# DIGITAL_OUTPUT1.net
KiCad netlist of a schematic drawn in Altium Designer
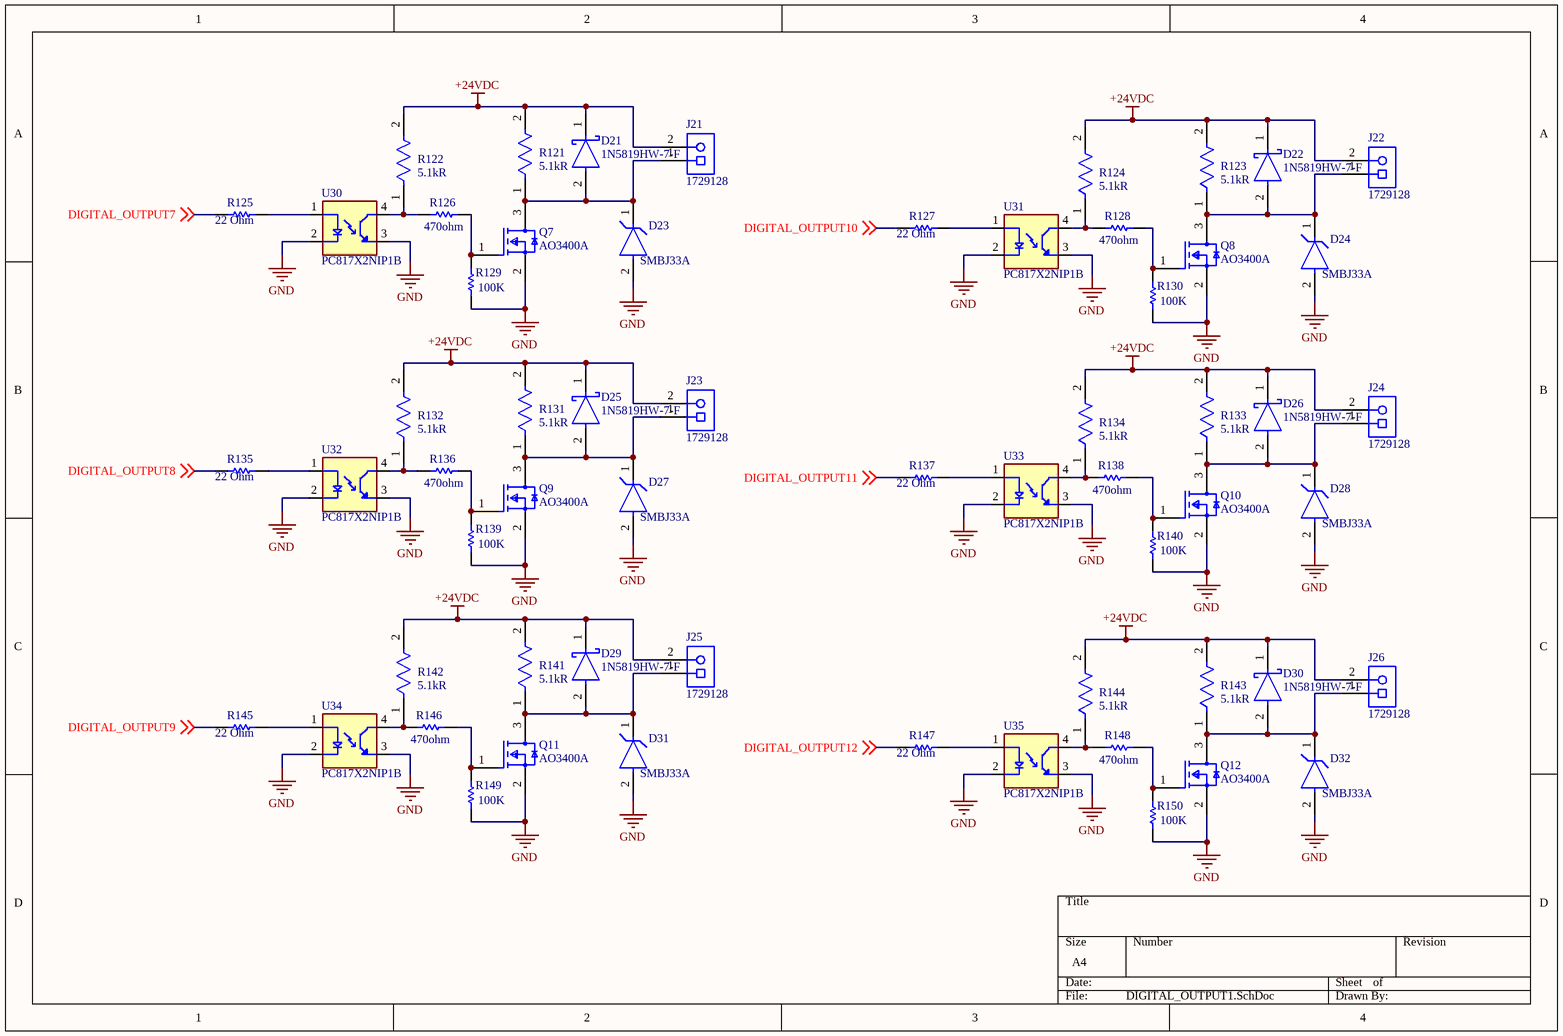
[diagram p0: DIGITAL_OUTPUT1.SchDoc]

(export (version "E")
  (design (tool "Eeschema 10.0.6"))
  (components
    (comp (ref "D21")
      (value "1N5819HW-7-F")
      (footprint "FP-SOD123-IPC_A")
      (description "DIODE SCHOTTKY 40V 1A SOD123")
      (libsource (lib "Altium Content Vault") (part "1d6ec82d83fb6aee721767c19dac4b9"))
    )
    (comp (ref "D22")
      (value "1N5819HW-7-F")
      (footprint "FP-SOD123-IPC_A")
      (description "DIODE SCHOTTKY 40V 1A SOD123")
      (libsource (lib "Altium Content Vault") (part "1d6ec82d83fb6aee721767c19dac4b9"))
    )
    (comp (ref "D23")
      (value "SMBJ33A")
      (footprint "FP-SMBJ-MFG")
      (description "TVS DIODE 33V 53.3V DO214AA")
      (fields
        (field (name "MANUFACTURER") "Littelfuse Inc")
        (field (name "OCTOPART") "https://octopart.com/smbj33a-littelfuse-350829")
      )
      (libsource (lib "Altium Content Vault") (part "f813f71cba58e380607f5dd3caf9714"))
    )
    (comp (ref "D24")
      (value "SMBJ33A")
      (footprint "FP-SMBJ-MFG")
      (description "TVS DIODE 33V 53.3V DO214AA")
      (fields
        (field (name "MANUFACTURER") "Littelfuse Inc")
        (field (name "OCTOPART") "https://octopart.com/smbj33a-littelfuse-350829")
      )
      (libsource (lib "Altium Content Vault") (part "f813f71cba58e380607f5dd3caf9714"))
    )
    (comp (ref "D25")
      (value "1N5819HW-7-F")
      (footprint "FP-SOD123-IPC_A")
      (description "DIODE SCHOTTKY 40V 1A SOD123")
      (libsource (lib "Altium Content Vault") (part "1d6ec82d83fb6aee721767c19dac4b9"))
    )
    (comp (ref "D26")
      (value "1N5819HW-7-F")
      (footprint "FP-SOD123-IPC_A")
      (description "DIODE SCHOTTKY 40V 1A SOD123")
      (libsource (lib "Altium Content Vault") (part "1d6ec82d83fb6aee721767c19dac4b9"))
    )
    (comp (ref "D27")
      (value "SMBJ33A")
      (footprint "FP-SMBJ-MFG")
      (description "TVS DIODE 33V 53.3V DO214AA")
      (fields
        (field (name "MANUFACTURER") "Littelfuse Inc")
        (field (name "OCTOPART") "https://octopart.com/smbj33a-littelfuse-350829")
      )
      (libsource (lib "Altium Content Vault") (part "f813f71cba58e380607f5dd3caf9714"))
    )
    (comp (ref "D28")
      (value "SMBJ33A")
      (footprint "FP-SMBJ-MFG")
      (description "TVS DIODE 33V 53.3V DO214AA")
      (fields
        (field (name "MANUFACTURER") "Littelfuse Inc")
        (field (name "OCTOPART") "https://octopart.com/smbj33a-littelfuse-350829")
      )
      (libsource (lib "Altium Content Vault") (part "f813f71cba58e380607f5dd3caf9714"))
    )
    (comp (ref "D29")
      (value "1N5819HW-7-F")
      (footprint "FP-SOD123-IPC_A")
      (description "DIODE SCHOTTKY 40V 1A SOD123")
      (libsource (lib "Altium Content Vault") (part "1d6ec82d83fb6aee721767c19dac4b9"))
    )
    (comp (ref "D30")
      (value "1N5819HW-7-F")
      (footprint "FP-SOD123-IPC_A")
      (description "DIODE SCHOTTKY 40V 1A SOD123")
      (libsource (lib "Altium Content Vault") (part "1d6ec82d83fb6aee721767c19dac4b9"))
    )
    (comp (ref "D31")
      (value "SMBJ33A")
      (footprint "FP-SMBJ-MFG")
      (description "TVS DIODE 33V 53.3V DO214AA")
      (fields
        (field (name "MANUFACTURER") "Littelfuse Inc")
        (field (name "OCTOPART") "https://octopart.com/smbj33a-littelfuse-350829")
      )
      (libsource (lib "Altium Content Vault") (part "f813f71cba58e380607f5dd3caf9714"))
    )
    (comp (ref "D32")
      (value "SMBJ33A")
      (footprint "FP-SMBJ-MFG")
      (description "TVS DIODE 33V 53.3V DO214AA")
      (fields
        (field (name "MANUFACTURER") "Littelfuse Inc")
        (field (name "OCTOPART") "https://octopart.com/smbj33a-littelfuse-350829")
      )
      (libsource (lib "Altium Content Vault") (part "f813f71cba58e380607f5dd3caf9714"))
    )
    (comp (ref "J21")
      (value "1729128")
      (footprint "PHOE-1729128-2_V")
      (description "PCB Terminal Block, 13.5 A, 400 V, 2-Pin THD, RoHS, Bulk")
      (fields (field (name "MANUFACTURER") "Phoenix Contact"))
      (libsource (lib "Altium Content Vault") (part "CN-2P-F-R2"))
    )
    (comp (ref "J22")
      (value "1729128")
      (footprint "PHOE-1729128-2_V")
      (description "PCB Terminal Block, 13.5 A, 400 V, 2-Pin THD, RoHS, Bulk")
      (fields (field (name "MANUFACTURER") "Phoenix Contact"))
      (libsource (lib "Altium Content Vault") (part "CN-2P-F-R2"))
    )
    (comp (ref "J23")
      (value "1729128")
      (footprint "PHOE-1729128-2_V")
      (description "PCB Terminal Block, 13.5 A, 400 V, 2-Pin THD, RoHS, Bulk")
      (fields (field (name "MANUFACTURER") "Phoenix Contact"))
      (libsource (lib "Altium Content Vault") (part "CN-2P-F-R2"))
    )
    (comp (ref "J24")
      (value "1729128")
      (footprint "PHOE-1729128-2_V")
      (description "PCB Terminal Block, 13.5 A, 400 V, 2-Pin THD, RoHS, Bulk")
      (fields (field (name "MANUFACTURER") "Phoenix Contact"))
      (libsource (lib "Altium Content Vault") (part "CN-2P-F-R2"))
    )
    (comp (ref "J25")
      (value "1729128")
      (footprint "PHOE-1729128-2_V")
      (description "PCB Terminal Block, 13.5 A, 400 V, 2-Pin THD, RoHS, Bulk")
      (fields (field (name "MANUFACTURER") "Phoenix Contact"))
      (libsource (lib "Altium Content Vault") (part "CN-2P-F-R2"))
    )
    (comp (ref "J26")
      (value "1729128")
      (footprint "PHOE-1729128-2_V")
      (description "PCB Terminal Block, 13.5 A, 400 V, 2-Pin THD, RoHS, Bulk")
      (fields (field (name "MANUFACTURER") "Phoenix Contact"))
      (libsource (lib "Altium Content Vault") (part "CN-2P-F-R2"))
    )
    (comp (ref "Q7")
      (value "AO3400A")
      (footprint "FP-SOT23-MFG")
      (description "MOSFET N-CH 30V 5.7A SOT23")
      (libsource (lib "Altium Content Vault") (part "0a9ea7c96deaaede766a5b531c28de0"))
    )
    (comp (ref "Q8")
      (value "AO3400A")
      (footprint "FP-SOT23-MFG")
      (description "MOSFET N-CH 30V 5.7A SOT23")
      (libsource (lib "Altium Content Vault") (part "0a9ea7c96deaaede766a5b531c28de0"))
    )
    (comp (ref "Q9")
      (value "AO3400A")
      (footprint "FP-SOT23-MFG")
      (description "MOSFET N-CH 30V 5.7A SOT23")
      (libsource (lib "Altium Content Vault") (part "0a9ea7c96deaaede766a5b531c28de0"))
    )
    (comp (ref "Q10")
      (value "AO3400A")
      (footprint "FP-SOT23-MFG")
      (description "MOSFET N-CH 30V 5.7A SOT23")
      (libsource (lib "Altium Content Vault") (part "0a9ea7c96deaaede766a5b531c28de0"))
    )
    (comp (ref "Q11")
      (value "AO3400A")
      (footprint "FP-SOT23-MFG")
      (description "MOSFET N-CH 30V 5.7A SOT23")
      (libsource (lib "Altium Content Vault") (part "0a9ea7c96deaaede766a5b531c28de0"))
    )
    (comp (ref "Q12")
      (value "AO3400A")
      (footprint "FP-SOT23-MFG")
      (description "MOSFET N-CH 30V 5.7A SOT23")
      (libsource (lib "Altium Content Vault") (part "0a9ea7c96deaaede766a5b531c28de0"))
    )
    (comp (ref "R121")
      (value "CRCW06035K10FKEA")
      (footprint "FP-CRCW0603-e3-IPC_C")
      (description "RES Thick Film, 5.1kΩ, 1%, 0.1W, 100ppm/°C, 0603")
      (fields (field (name "TOLERANCE") "1%") (field (name "RESISTANCE") "5.1kR"))
      (libsource (lib "Altium Content Vault") (part "1029c3af85768c4190bb7ad29bc67b5"))
    )
    (comp (ref "R122")
      (value "CRCW06035K10FKEA")
      (footprint "FP-CRCW0603-e3-IPC_C")
      (description "RES Thick Film, 5.1kΩ, 1%, 0.1W, 100ppm/°C, 0603")
      (fields (field (name "TOLERANCE") "1%") (field (name "RESISTANCE") "5.1kR"))
      (libsource (lib "Altium Content Vault") (part "1029c3af85768c4190bb7ad29bc67b5"))
    )
    (comp (ref "R123")
      (value "CRCW06035K10FKEA")
      (footprint "FP-CRCW0603-e3-IPC_C")
      (description "RES Thick Film, 5.1kΩ, 1%, 0.1W, 100ppm/°C, 0603")
      (fields (field (name "TOLERANCE") "1%") (field (name "RESISTANCE") "5.1kR"))
      (libsource (lib "Altium Content Vault") (part "1029c3af85768c4190bb7ad29bc67b5"))
    )
    (comp (ref "R124")
      (value "CRCW06035K10FKEA")
      (footprint "FP-CRCW0603-e3-IPC_C")
      (description "RES Thick Film, 5.1kΩ, 1%, 0.1W, 100ppm/°C, 0603")
      (fields (field (name "TOLERANCE") "1%") (field (name "RESISTANCE") "5.1kR"))
      (libsource (lib "Altium Content Vault") (part "1029c3af85768c4190bb7ad29bc67b5"))
    )
    (comp (ref "R125")
      (value "ERJ-3EKF2200V")
      (footprint "RESC1608X55X30LL15T15")
      (description "Chip Resistor, 220 Ohm, +/- 1%, 0.1 W, -55 to 155 degC, 0603 (1608 Metric), RoHS, Tape and Reel")
      (fields (field (name "RESISTANCE") "22 Ohm") (field (name "TOLERANCE") "1%"))
      (libsource (lib "Altium Content Vault") (part "RES-2"))
    )
    (comp (ref "R126")
      (value "RC0805FR-07470RL")
      (footprint "RESC2013X60X35LL10T20")
      (description "Chip Resistor, 470 Ohm, +/- 1%, 125 mW, -55 to 155 degC, 0805 (2012 Metric), RoHS, Tape and Reel")
      (fields (field (name "MANUFACTURER") "Yageo") (field (name "RESISTANCE") "470ohm"))
      (libsource (lib "Altium Content Vault") (part "RES-2"))
    )
    (comp (ref "R127")
      (value "ERJ-3EKF2200V")
      (footprint "RESC1608X55X30LL15T15")
      (description "Chip Resistor, 220 Ohm, +/- 1%, 0.1 W, -55 to 155 degC, 0603 (1608 Metric), RoHS, Tape and Reel")
      (fields (field (name "RESISTANCE") "22 Ohm") (field (name "TOLERANCE") "1%"))
      (libsource (lib "Altium Content Vault") (part "RES-2"))
    )
    (comp (ref "R128")
      (value "RC0805FR-07470RL")
      (footprint "RESC2013X60X35LL10T20")
      (description "Chip Resistor, 470 Ohm, +/- 1%, 125 mW, -55 to 155 degC, 0805 (2012 Metric), RoHS, Tape and Reel")
      (fields (field (name "MANUFACTURER") "Yageo") (field (name "RESISTANCE") "470ohm"))
      (libsource (lib "Altium Content Vault") (part "RES-2"))
    )
    (comp (ref "R129")
      (value "100K")
      (footprint "RESC2013X50X30ML20T20")
      (fields (field (name "MANUFACTURER") "Vishay Dale") (field (name "PART NUMBER") "CRCW0805100KJNEA"))
      (libsource (lib "Altium Content Vault") (part "RES"))
    )
    (comp (ref "R130")
      (value "100K")
      (footprint "RESC2013X50X30ML20T20")
      (fields (field (name "MANUFACTURER") "Vishay Dale") (field (name "PART NUMBER") "CRCW0805100KJNEA"))
      (libsource (lib "Altium Content Vault") (part "RES"))
    )
    (comp (ref "R131")
      (value "CRCW06035K10FKEA")
      (footprint "FP-CRCW0603-e3-IPC_C")
      (description "RES Thick Film, 5.1kΩ, 1%, 0.1W, 100ppm/°C, 0603")
      (fields (field (name "TOLERANCE") "1%") (field (name "RESISTANCE") "5.1kR"))
      (libsource (lib "Altium Content Vault") (part "1029c3af85768c4190bb7ad29bc67b5"))
    )
    (comp (ref "R132")
      (value "CRCW06035K10FKEA")
      (footprint "FP-CRCW0603-e3-IPC_C")
      (description "RES Thick Film, 5.1kΩ, 1%, 0.1W, 100ppm/°C, 0603")
      (fields (field (name "TOLERANCE") "1%") (field (name "RESISTANCE") "5.1kR"))
      (libsource (lib "Altium Content Vault") (part "1029c3af85768c4190bb7ad29bc67b5"))
    )
    (comp (ref "R133")
      (value "CRCW06035K10FKEA")
      (footprint "FP-CRCW0603-e3-IPC_C")
      (description "RES Thick Film, 5.1kΩ, 1%, 0.1W, 100ppm/°C, 0603")
      (fields (field (name "TOLERANCE") "1%") (field (name "RESISTANCE") "5.1kR"))
      (libsource (lib "Altium Content Vault") (part "1029c3af85768c4190bb7ad29bc67b5"))
    )
    (comp (ref "R134")
      (value "CRCW06035K10FKEA")
      (footprint "FP-CRCW0603-e3-IPC_C")
      (description "RES Thick Film, 5.1kΩ, 1%, 0.1W, 100ppm/°C, 0603")
      (fields (field (name "TOLERANCE") "1%") (field (name "RESISTANCE") "5.1kR"))
      (libsource (lib "Altium Content Vault") (part "1029c3af85768c4190bb7ad29bc67b5"))
    )
    (comp (ref "R135")
      (value "ERJ-3EKF2200V")
      (footprint "RESC1608X55X30LL15T15")
      (description "Chip Resistor, 220 Ohm, +/- 1%, 0.1 W, -55 to 155 degC, 0603 (1608 Metric), RoHS, Tape and Reel")
      (fields (field (name "RESISTANCE") "22 Ohm") (field (name "TOLERANCE") "1%"))
      (libsource (lib "Altium Content Vault") (part "RES-2"))
    )
    (comp (ref "R136")
      (value "RC0805FR-07470RL")
      (footprint "RESC2013X60X35LL10T20")
      (description "Chip Resistor, 470 Ohm, +/- 1%, 125 mW, -55 to 155 degC, 0805 (2012 Metric), RoHS, Tape and Reel")
      (fields (field (name "MANUFACTURER") "Yageo") (field (name "RESISTANCE") "470ohm"))
      (libsource (lib "Altium Content Vault") (part "RES-2"))
    )
    (comp (ref "R137")
      (value "ERJ-3EKF2200V")
      (footprint "RESC1608X55X30LL15T15")
      (description "Chip Resistor, 220 Ohm, +/- 1%, 0.1 W, -55 to 155 degC, 0603 (1608 Metric), RoHS, Tape and Reel")
      (fields (field (name "RESISTANCE") "22 Ohm") (field (name "TOLERANCE") "1%"))
      (libsource (lib "Altium Content Vault") (part "RES-2"))
    )
    (comp (ref "R138")
      (value "RC0805FR-07470RL")
      (footprint "RESC2013X60X35LL10T20")
      (description "Chip Resistor, 470 Ohm, +/- 1%, 125 mW, -55 to 155 degC, 0805 (2012 Metric), RoHS, Tape and Reel")
      (fields (field (name "MANUFACTURER") "Yageo") (field (name "RESISTANCE") "470ohm"))
      (libsource (lib "Altium Content Vault") (part "RES-2"))
    )
    (comp (ref "R139")
      (value "100K")
      (footprint "RESC2013X50X30ML20T20")
      (fields (field (name "MANUFACTURER") "Vishay Dale") (field (name "PART NUMBER") "CRCW0805100KJNEA"))
      (libsource (lib "Altium Content Vault") (part "RES"))
    )
    (comp (ref "R140")
      (value "100K")
      (footprint "RESC2013X50X30ML20T20")
      (fields (field (name "MANUFACTURER") "Vishay Dale") (field (name "PART NUMBER") "CRCW0805100KJNEA"))
      (libsource (lib "Altium Content Vault") (part "RES"))
    )
    (comp (ref "R141")
      (value "CRCW06035K10FKEA")
      (footprint "FP-CRCW0603-e3-IPC_C")
      (description "RES Thick Film, 5.1kΩ, 1%, 0.1W, 100ppm/°C, 0603")
      (fields (field (name "TOLERANCE") "1%") (field (name "RESISTANCE") "5.1kR"))
      (libsource (lib "Altium Content Vault") (part "1029c3af85768c4190bb7ad29bc67b5"))
    )
    (comp (ref "R142")
      (value "CRCW06035K10FKEA")
      (footprint "FP-CRCW0603-e3-IPC_C")
      (description "RES Thick Film, 5.1kΩ, 1%, 0.1W, 100ppm/°C, 0603")
      (fields (field (name "TOLERANCE") "1%") (field (name "RESISTANCE") "5.1kR"))
      (libsource (lib "Altium Content Vault") (part "1029c3af85768c4190bb7ad29bc67b5"))
    )
    (comp (ref "R143")
      (value "CRCW06035K10FKEA")
      (footprint "FP-CRCW0603-e3-IPC_C")
      (description "RES Thick Film, 5.1kΩ, 1%, 0.1W, 100ppm/°C, 0603")
      (fields (field (name "TOLERANCE") "1%") (field (name "RESISTANCE") "5.1kR"))
      (libsource (lib "Altium Content Vault") (part "1029c3af85768c4190bb7ad29bc67b5"))
    )
    (comp (ref "R144")
      (value "CRCW06035K10FKEA")
      (footprint "FP-CRCW0603-e3-IPC_C")
      (description "RES Thick Film, 5.1kΩ, 1%, 0.1W, 100ppm/°C, 0603")
      (fields (field (name "TOLERANCE") "1%") (field (name "RESISTANCE") "5.1kR"))
      (libsource (lib "Altium Content Vault") (part "1029c3af85768c4190bb7ad29bc67b5"))
    )
    (comp (ref "R145")
      (value "ERJ-3EKF2200V")
      (footprint "RESC1608X55X30LL15T15")
      (description "Chip Resistor, 220 Ohm, +/- 1%, 0.1 W, -55 to 155 degC, 0603 (1608 Metric), RoHS, Tape and Reel")
      (fields (field (name "RESISTANCE") "22 Ohm") (field (name "TOLERANCE") "1%"))
      (libsource (lib "Altium Content Vault") (part "RES-2"))
    )
    (comp (ref "R146")
      (value "RC0805FR-07470RL")
      (footprint "RESC2013X60X35LL10T20")
      (description "Chip Resistor, 470 Ohm, +/- 1%, 125 mW, -55 to 155 degC, 0805 (2012 Metric), RoHS, Tape and Reel")
      (fields (field (name "MANUFACTURER") "Yageo") (field (name "RESISTANCE") "470ohm"))
      (libsource (lib "Altium Content Vault") (part "RES-2"))
    )
    (comp (ref "R147")
      (value "ERJ-3EKF2200V")
      (footprint "RESC1608X55X30LL15T15")
      (description "Chip Resistor, 220 Ohm, +/- 1%, 0.1 W, -55 to 155 degC, 0603 (1608 Metric), RoHS, Tape and Reel")
      (fields (field (name "RESISTANCE") "22 Ohm") (field (name "TOLERANCE") "1%"))
      (libsource (lib "Altium Content Vault") (part "RES-2"))
    )
    (comp (ref "R148")
      (value "RC0805FR-07470RL")
      (footprint "RESC2013X60X35LL10T20")
      (description "Chip Resistor, 470 Ohm, +/- 1%, 125 mW, -55 to 155 degC, 0805 (2012 Metric), RoHS, Tape and Reel")
      (fields (field (name "MANUFACTURER") "Yageo") (field (name "RESISTANCE") "470ohm"))
      (libsource (lib "Altium Content Vault") (part "RES-2"))
    )
    (comp (ref "R149")
      (value "100K")
      (footprint "RESC2013X50X30ML20T20")
      (fields (field (name "MANUFACTURER") "Vishay Dale") (field (name "PART NUMBER") "CRCW0805100KJNEA"))
      (libsource (lib "Altium Content Vault") (part "RES"))
    )
    (comp (ref "R150")
      (value "100K")
      (footprint "RESC2013X50X30ML20T20")
      (fields (field (name "MANUFACTURER") "Vishay Dale") (field (name "PART NUMBER") "CRCW0805100KJNEA"))
      (libsource (lib "Altium Content Vault") (part "RES"))
    )
    (comp (ref "U30")
      (value "PC817X2NIP1B")
      (footprint "SOIC254P960X420-4N")
      (description "Optocoupler DC-IN 1-CH Transistor DC-OUT 4-Pin DIP SMD T/R")
      (fields (field (name "MF") "Sharp Microelectronics"))
      (libsource (lib "PC817X2NIP1B") (part "PC817X2NIP1B"))
    )
    (comp (ref "U31")
      (value "PC817X2NIP1B")
      (footprint "SOIC254P960X420-4N")
      (description "Optocoupler DC-IN 1-CH Transistor DC-OUT 4-Pin DIP SMD T/R")
      (fields (field (name "MF") "Sharp Microelectronics"))
      (libsource (lib "PC817X2NIP1B") (part "PC817X2NIP1B"))
    )
    (comp (ref "U32")
      (value "PC817X2NIP1B")
      (footprint "SOIC254P960X420-4N")
      (description "Optocoupler DC-IN 1-CH Transistor DC-OUT 4-Pin DIP SMD T/R")
      (fields (field (name "MF") "Sharp Microelectronics"))
      (libsource (lib "PC817X2NIP1B") (part "PC817X2NIP1B"))
    )
    (comp (ref "U33")
      (value "PC817X2NIP1B")
      (footprint "SOIC254P960X420-4N")
      (description "Optocoupler DC-IN 1-CH Transistor DC-OUT 4-Pin DIP SMD T/R")
      (fields (field (name "MF") "Sharp Microelectronics"))
      (libsource (lib "PC817X2NIP1B") (part "PC817X2NIP1B"))
    )
    (comp (ref "U34")
      (value "PC817X2NIP1B")
      (footprint "SOIC254P960X420-4N")
      (description "Optocoupler DC-IN 1-CH Transistor DC-OUT 4-Pin DIP SMD T/R")
      (fields (field (name "MF") "Sharp Microelectronics"))
      (libsource (lib "PC817X2NIP1B") (part "PC817X2NIP1B"))
    )
    (comp (ref "U35")
      (value "PC817X2NIP1B")
      (footprint "SOIC254P960X420-4N")
      (description "Optocoupler DC-IN 1-CH Transistor DC-OUT 4-Pin DIP SMD T/R")
      (fields (field (name "MF") "Sharp Microelectronics"))
      (libsource (lib "PC817X2NIP1B") (part "PC817X2NIP1B"))
    )
  )
  (nets
    (net (code "1") (name "+24VDC") (class "Default")
      (node (ref "D21") (pin "1") (pinfunction "C_1") (pintype "passive"))
      (node (ref "D22") (pin "1") (pinfunction "C_1") (pintype "passive"))
      (node (ref "D25") (pin "1") (pinfunction "C_1") (pintype "passive"))
      (node (ref "D26") (pin "1") (pinfunction "C_1") (pintype "passive"))
      (node (ref "D29") (pin "1") (pinfunction "C_1") (pintype "passive"))
      (node (ref "D30") (pin "1") (pinfunction "C_1") (pintype "passive"))
      (node (ref "J21") (pin "2") (pinfunction "2_2") (pintype "passive"))
      (node (ref "J22") (pin "2") (pinfunction "2_2") (pintype "passive"))
      (node (ref "J23") (pin "2") (pinfunction "2_2") (pintype "passive"))
      (node (ref "J24") (pin "2") (pinfunction "2_2") (pintype "passive"))
      (node (ref "J25") (pin "2") (pinfunction "2_2") (pintype "passive"))
      (node (ref "J26") (pin "2") (pinfunction "2_2") (pintype "passive"))
      (node (ref "R121") (pin "2") (pinfunction "2_2") (pintype "passive"))
      (node (ref "R122") (pin "2") (pinfunction "2_2") (pintype "passive"))
      (node (ref "R123") (pin "2") (pinfunction "2_2") (pintype "passive"))
      (node (ref "R124") (pin "2") (pinfunction "2_2") (pintype "passive"))
      (node (ref "R131") (pin "2") (pinfunction "2_2") (pintype "passive"))
      (node (ref "R132") (pin "2") (pinfunction "2_2") (pintype "passive"))
      (node (ref "R133") (pin "2") (pinfunction "2_2") (pintype "passive"))
      (node (ref "R134") (pin "2") (pinfunction "2_2") (pintype "passive"))
      (node (ref "R141") (pin "2") (pinfunction "2_2") (pintype "passive"))
      (node (ref "R142") (pin "2") (pinfunction "2_2") (pintype "passive"))
      (node (ref "R143") (pin "2") (pinfunction "2_2") (pintype "passive"))
      (node (ref "R144") (pin "2") (pinfunction "2_2") (pintype "passive"))
    )
    (net (code "2") (name "DIGITAL_OUTPUT7") (class "Default")
      (node (ref "R125") (pin "1") (pinfunction "1_1") (pintype "passive"))
    )
    (net (code "3") (name "DIGITAL_OUTPUT8") (class "Default")
      (node (ref "R135") (pin "1") (pinfunction "1_1") (pintype "passive"))
    )
    (net (code "4") (name "DIGITAL_OUTPUT9") (class "Default")
      (node (ref "R145") (pin "1") (pinfunction "1_1") (pintype "passive"))
    )
    (net (code "5") (name "DIGITAL_OUTPUT10") (class "Default")
      (node (ref "R127") (pin "1") (pinfunction "1_1") (pintype "passive"))
    )
    (net (code "6") (name "DIGITAL_OUTPUT11") (class "Default")
      (node (ref "R137") (pin "1") (pinfunction "1_1") (pintype "passive"))
    )
    (net (code "7") (name "DIGITAL_OUTPUT12") (class "Default")
      (node (ref "R147") (pin "1") (pinfunction "1_1") (pintype "passive"))
    )
    (net (code "8") (name "GND") (class "Default")
      (node (ref "D23") (pin "2") (pinfunction "A_2") (pintype "passive"))
      (node (ref "D24") (pin "2") (pinfunction "A_2") (pintype "passive"))
      (node (ref "D27") (pin "2") (pinfunction "A_2") (pintype "passive"))
      (node (ref "D28") (pin "2") (pinfunction "A_2") (pintype "passive"))
      (node (ref "D31") (pin "2") (pinfunction "A_2") (pintype "passive"))
      (node (ref "D32") (pin "2") (pinfunction "A_2") (pintype "passive"))
      (node (ref "Q10") (pin "2") (pinfunction "S_2") (pintype "passive"))
      (node (ref "Q11") (pin "2") (pinfunction "S_2") (pintype "passive"))
      (node (ref "Q12") (pin "2") (pinfunction "S_2") (pintype "passive"))
      (node (ref "Q7") (pin "2") (pinfunction "S_2") (pintype "passive"))
      (node (ref "Q8") (pin "2") (pinfunction "S_2") (pintype "passive"))
      (node (ref "Q9") (pin "2") (pinfunction "S_2") (pintype "passive"))
      (node (ref "R129") (pin "1") (pinfunction "1_1") (pintype "passive"))
      (node (ref "R130") (pin "1") (pinfunction "1_1") (pintype "passive"))
      (node (ref "R139") (pin "1") (pinfunction "1_1") (pintype "passive"))
      (node (ref "R140") (pin "1") (pinfunction "1_1") (pintype "passive"))
      (node (ref "R149") (pin "1") (pinfunction "1_1") (pintype "passive"))
      (node (ref "R150") (pin "1") (pinfunction "1_1") (pintype "passive"))
      (node (ref "U30") (pin "2") (pinfunction "C_2") (pintype "passive"))
      (node (ref "U30") (pin "3") (pinfunction "ET_3") (pintype "passive"))
      (node (ref "U31") (pin "2") (pinfunction "C_2") (pintype "passive"))
      (node (ref "U31") (pin "3") (pinfunction "ET_3") (pintype "passive"))
      (node (ref "U32") (pin "2") (pinfunction "C_2") (pintype "passive"))
      (node (ref "U32") (pin "3") (pinfunction "ET_3") (pintype "passive"))
      (node (ref "U33") (pin "2") (pinfunction "C_2") (pintype "passive"))
      (node (ref "U33") (pin "3") (pinfunction "ET_3") (pintype "passive"))
      (node (ref "U34") (pin "2") (pinfunction "C_2") (pintype "passive"))
      (node (ref "U34") (pin "3") (pinfunction "ET_3") (pintype "passive"))
      (node (ref "U35") (pin "2") (pinfunction "C_2") (pintype "passive"))
      (node (ref "U35") (pin "3") (pinfunction "ET_3") (pintype "passive"))
    )
    (net (code "9") (name "Net-(D21-A)") (class "Default")
      (node (ref "D21") (pin "2") (pinfunction "A_2") (pintype "passive"))
      (node (ref "D23") (pin "1") (pinfunction "C_1") (pintype "passive"))
      (node (ref "J21") (pin "1") (pinfunction "1_1") (pintype "passive"))
      (node (ref "Q7") (pin "3") (pinfunction "D_3") (pintype "passive"))
      (node (ref "R121") (pin "1") (pinfunction "1_1") (pintype "passive"))
    )
    (net (code "10") (name "Net-(D22-A)") (class "Default")
      (node (ref "D22") (pin "2") (pinfunction "A_2") (pintype "passive"))
      (node (ref "D24") (pin "1") (pinfunction "C_1") (pintype "passive"))
      (node (ref "J22") (pin "1") (pinfunction "1_1") (pintype "passive"))
      (node (ref "Q8") (pin "3") (pinfunction "D_3") (pintype "passive"))
      (node (ref "R123") (pin "1") (pinfunction "1_1") (pintype "passive"))
    )
    (net (code "11") (name "Net-(D25-A)") (class "Default")
      (node (ref "D25") (pin "2") (pinfunction "A_2") (pintype "passive"))
      (node (ref "D27") (pin "1") (pinfunction "C_1") (pintype "passive"))
      (node (ref "J23") (pin "1") (pinfunction "1_1") (pintype "passive"))
      (node (ref "Q9") (pin "3") (pinfunction "D_3") (pintype "passive"))
      (node (ref "R131") (pin "1") (pinfunction "1_1") (pintype "passive"))
    )
    (net (code "12") (name "Net-(D26-A)") (class "Default")
      (node (ref "D26") (pin "2") (pinfunction "A_2") (pintype "passive"))
      (node (ref "D28") (pin "1") (pinfunction "C_1") (pintype "passive"))
      (node (ref "J24") (pin "1") (pinfunction "1_1") (pintype "passive"))
      (node (ref "Q10") (pin "3") (pinfunction "D_3") (pintype "passive"))
      (node (ref "R133") (pin "1") (pinfunction "1_1") (pintype "passive"))
    )
    (net (code "13") (name "Net-(D29-A)") (class "Default")
      (node (ref "D29") (pin "2") (pinfunction "A_2") (pintype "passive"))
      (node (ref "D31") (pin "1") (pinfunction "C_1") (pintype "passive"))
      (node (ref "J25") (pin "1") (pinfunction "1_1") (pintype "passive"))
      (node (ref "Q11") (pin "3") (pinfunction "D_3") (pintype "passive"))
      (node (ref "R141") (pin "1") (pinfunction "1_1") (pintype "passive"))
    )
    (net (code "14") (name "Net-(D30-A)") (class "Default")
      (node (ref "D30") (pin "2") (pinfunction "A_2") (pintype "passive"))
      (node (ref "D32") (pin "1") (pinfunction "C_1") (pintype "passive"))
      (node (ref "J26") (pin "1") (pinfunction "1_1") (pintype "passive"))
      (node (ref "Q12") (pin "3") (pinfunction "D_3") (pintype "passive"))
      (node (ref "R143") (pin "1") (pinfunction "1_1") (pintype "passive"))
    )
    (net (code "15") (name "Net-(Q7-G)") (class "Default")
      (node (ref "Q7") (pin "1") (pinfunction "G_1") (pintype "passive"))
      (node (ref "R126") (pin "2") (pinfunction "2_2") (pintype "passive"))
      (node (ref "R129") (pin "2") (pinfunction "2_2") (pintype "passive"))
    )
    (net (code "16") (name "Net-(Q8-G)") (class "Default")
      (node (ref "Q8") (pin "1") (pinfunction "G_1") (pintype "passive"))
      (node (ref "R128") (pin "2") (pinfunction "2_2") (pintype "passive"))
      (node (ref "R130") (pin "2") (pinfunction "2_2") (pintype "passive"))
    )
    (net (code "17") (name "Net-(Q9-G)") (class "Default")
      (node (ref "Q9") (pin "1") (pinfunction "G_1") (pintype "passive"))
      (node (ref "R136") (pin "2") (pinfunction "2_2") (pintype "passive"))
      (node (ref "R139") (pin "2") (pinfunction "2_2") (pintype "passive"))
    )
    (net (code "18") (name "Net-(Q10-G)") (class "Default")
      (node (ref "Q10") (pin "1") (pinfunction "G_1") (pintype "passive"))
      (node (ref "R138") (pin "2") (pinfunction "2_2") (pintype "passive"))
      (node (ref "R140") (pin "2") (pinfunction "2_2") (pintype "passive"))
    )
    (net (code "19") (name "Net-(Q11-G)") (class "Default")
      (node (ref "Q11") (pin "1") (pinfunction "G_1") (pintype "passive"))
      (node (ref "R146") (pin "2") (pinfunction "2_2") (pintype "passive"))
      (node (ref "R149") (pin "2") (pinfunction "2_2") (pintype "passive"))
    )
    (net (code "20") (name "Net-(Q12-G)") (class "Default")
      (node (ref "Q12") (pin "1") (pinfunction "G_1") (pintype "passive"))
      (node (ref "R148") (pin "2") (pinfunction "2_2") (pintype "passive"))
      (node (ref "R150") (pin "2") (pinfunction "2_2") (pintype "passive"))
    )
    (net (code "21") (name "Net-(U30-A)") (class "Default")
      (node (ref "R125") (pin "2") (pinfunction "2_2") (pintype "passive"))
      (node (ref "U30") (pin "1") (pinfunction "A_1") (pintype "passive"))
    )
    (net (code "22") (name "Net-(U30-CT)") (class "Default")
      (node (ref "R122") (pin "1") (pinfunction "1_1") (pintype "passive"))
      (node (ref "R126") (pin "1") (pinfunction "1_1") (pintype "passive"))
      (node (ref "U30") (pin "4") (pinfunction "CT_4") (pintype "passive"))
    )
    (net (code "23") (name "Net-(U31-A)") (class "Default")
      (node (ref "R127") (pin "2") (pinfunction "2_2") (pintype "passive"))
      (node (ref "U31") (pin "1") (pinfunction "A_1") (pintype "passive"))
    )
    (net (code "24") (name "Net-(U31-CT)") (class "Default")
      (node (ref "R124") (pin "1") (pinfunction "1_1") (pintype "passive"))
      (node (ref "R128") (pin "1") (pinfunction "1_1") (pintype "passive"))
      (node (ref "U31") (pin "4") (pinfunction "CT_4") (pintype "passive"))
    )
    (net (code "25") (name "Net-(U32-A)") (class "Default")
      (node (ref "R135") (pin "2") (pinfunction "2_2") (pintype "passive"))
      (node (ref "U32") (pin "1") (pinfunction "A_1") (pintype "passive"))
    )
    (net (code "26") (name "Net-(U32-CT)") (class "Default")
      (node (ref "R132") (pin "1") (pinfunction "1_1") (pintype "passive"))
      (node (ref "R136") (pin "1") (pinfunction "1_1") (pintype "passive"))
      (node (ref "U32") (pin "4") (pinfunction "CT_4") (pintype "passive"))
    )
    (net (code "27") (name "Net-(U33-A)") (class "Default")
      (node (ref "R137") (pin "2") (pinfunction "2_2") (pintype "passive"))
      (node (ref "U33") (pin "1") (pinfunction "A_1") (pintype "passive"))
    )
    (net (code "28") (name "Net-(U33-CT)") (class "Default")
      (node (ref "R134") (pin "1") (pinfunction "1_1") (pintype "passive"))
      (node (ref "R138") (pin "1") (pinfunction "1_1") (pintype "passive"))
      (node (ref "U33") (pin "4") (pinfunction "CT_4") (pintype "passive"))
    )
    (net (code "29") (name "Net-(U34-A)") (class "Default")
      (node (ref "R145") (pin "2") (pinfunction "2_2") (pintype "passive"))
      (node (ref "U34") (pin "1") (pinfunction "A_1") (pintype "passive"))
    )
    (net (code "30") (name "Net-(U34-CT)") (class "Default")
      (node (ref "R142") (pin "1") (pinfunction "1_1") (pintype "passive"))
      (node (ref "R146") (pin "1") (pinfunction "1_1") (pintype "passive"))
      (node (ref "U34") (pin "4") (pinfunction "CT_4") (pintype "passive"))
    )
    (net (code "31") (name "Net-(U35-A)") (class "Default")
      (node (ref "R147") (pin "2") (pinfunction "2_2") (pintype "passive"))
      (node (ref "U35") (pin "1") (pinfunction "A_1") (pintype "passive"))
    )
    (net (code "32") (name "Net-(U35-CT)") (class "Default")
      (node (ref "R144") (pin "1") (pinfunction "1_1") (pintype "passive"))
      (node (ref "R148") (pin "1") (pinfunction "1_1") (pintype "passive"))
      (node (ref "U35") (pin "4") (pinfunction "CT_4") (pintype "passive"))
    )
  )
)
